# ee453_pcb_Schulz.net
KiCad netlist of a schematic drawn in Altium Designer
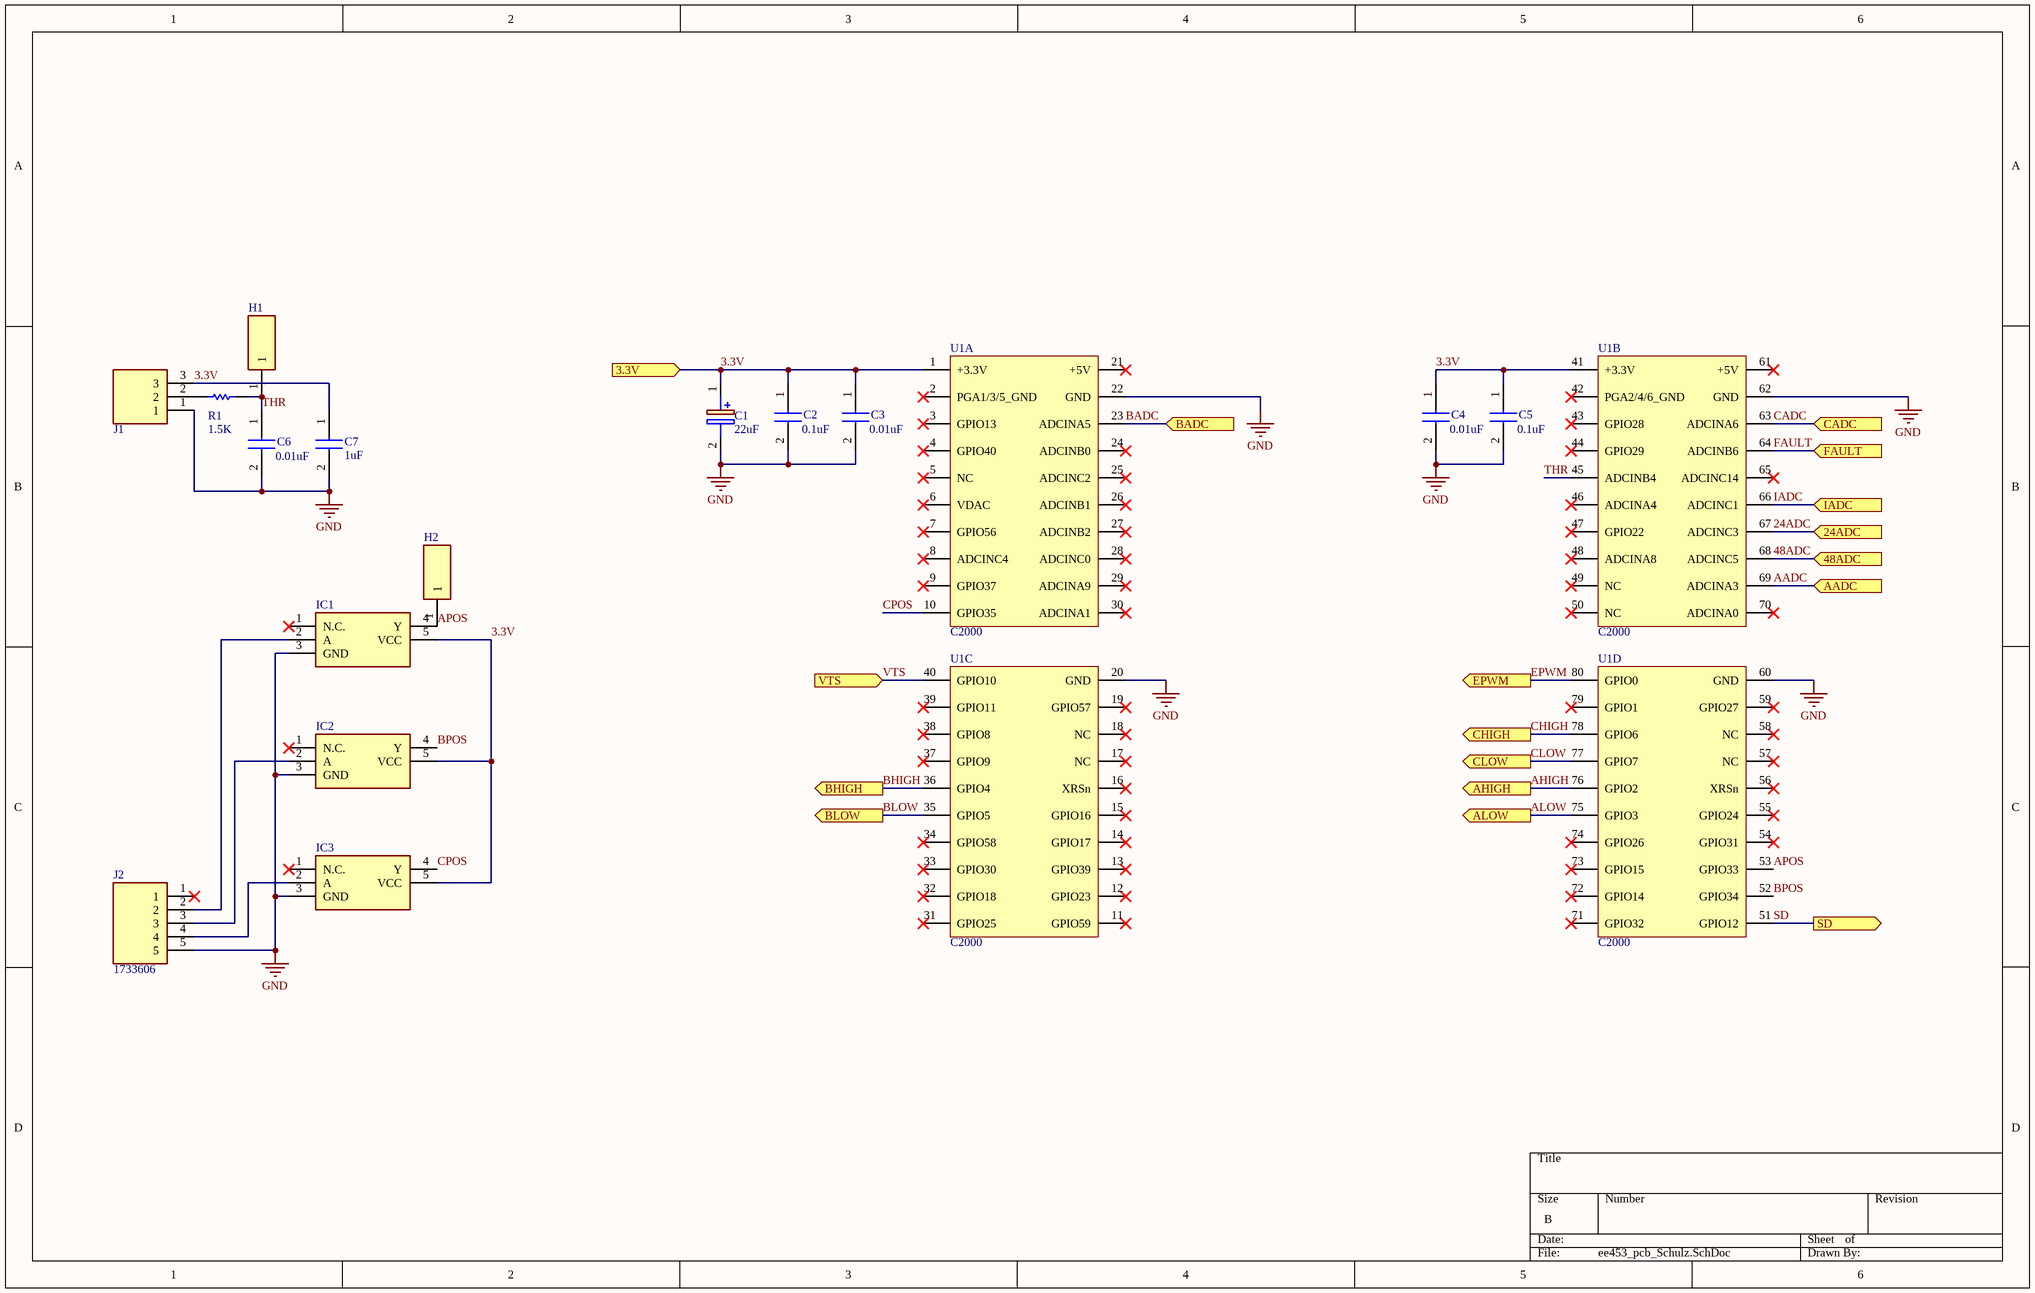
[diagram p0: ee453_pcb_Schulz.SchDoc]

(export (version "E")
  (design (tool "Eeschema 10.0.6"))
  (components
    (comp (ref "C1")
      (value "22uF")
      (footprint "CAPPRD250W50D800H800")
      (description "Capacitor Polarised 10V")
      (fields
        (field (name "MANUFACTURER_PART_NUMBER") "ECE-A1AKA220I")
        (field (name "MOUSER PART NUMBER") "667-ECE-A1AKA220I")
      )
      (libsource (lib "ee_453_Schulz") (part "ECE-A1AKA220I"))
    )
    (comp (ref "C2")
      (value "0.1uF")
      (footprint "CAPC1005X55N")
      (description "Capacitor 10V")
      (fields
        (field (name "MANUFACTURER_PART_NUMBER") "CC0402KRX7R6BB104")
        (field (name "MOUSER PART NUMBER") "603-CC402KRX7R6BB104")
      )
      (libsource (lib "ee_453_Schulz") (part "CC0402KRX7R6BB104"))
    )
    (comp (ref "C3")
      (value "0.01uF")
      (footprint "CAPC0603X33N")
      (description "Capacitor 10V")
      (fields
        (field (name "MANUFACTURER_PART_NUMBER") "GRM033R71A103KA01D")
        (field (name "MOUSER PART NUMBER") "81-GRM033R71A103KA1D")
      )
      (libsource (lib "ee_453_Schulz") (part "GRM033R71A103KA01D"))
    )
    (comp (ref "C4")
      (value "0.01uF")
      (footprint "CAPC0603X33N")
      (description "Capacitor 10V")
      (fields
        (field (name "MANUFACTURER_PART_NUMBER") "GRM033R71A103KA01D")
        (field (name "MOUSER PART NUMBER") "81-GRM033R71A103KA1D")
      )
      (libsource (lib "ee_453_Schulz") (part "GRM033R71A103KA01D"))
    )
    (comp (ref "C5")
      (value "0.1uF")
      (footprint "CAPC1005X55N")
      (description "Capacitor 10V")
      (fields
        (field (name "MANUFACTURER_PART_NUMBER") "CC0402KRX7R6BB104")
        (field (name "MOUSER PART NUMBER") "603-CC402KRX7R6BB104")
      )
      (libsource (lib "ee_453_Schulz") (part "CC0402KRX7R6BB104"))
    )
    (comp (ref "C6")
      (value "0.01uF")
      (footprint "C315C103K5R5TA7990")
      (description "Capacitor 50V")
      (fields (field (name "MANUFACTURER_PART_NUMBER") "C315C103K5R5TA7990"))
      (libsource (lib "ee_453_Schulz") (part "C315C103K5R5TA7990"))
    )
    (comp (ref "C7")
      (value "1uF")
      (footprint "C330C105K5R5TA")
      (description "Capacitor 50V")
      (fields
        (field (name "MANUFACTURER_PART_NUMBER") "C330C105K5R5TA")
        (field (name "MOUSER PART NUMBER") "80-C330C105K5R")
      )
      (libsource (lib "ee_453_Schulz") (part "C330C105K5R5TA"))
    )
    (comp (ref "H1")
      (value "5003")
      (footprint "5003")
      (description "Hardware")
      (fields (field (name "MOUSER PART NUMBER") "534-5003"))
      (libsource (lib "ee_453_Schulz") (part "5003"))
    )
    (comp (ref "H2")
      (value "5003")
      (footprint "5003")
      (description "Hardware")
      (fields (field (name "MOUSER PART NUMBER") "534-5003"))
      (libsource (lib "ee_453_Schulz") (part "5003"))
    )
    (comp (ref "IC1")
      (value "SN74LV1T34DBVRG4")
      (footprint "SOT95P280X145-5N")
      (description "Integrated Circuit")
      (fields (field (name "MOUSER PART NUMBER") "595-SN74LV1T34DBVRG4"))
      (libsource (lib "ee_453_Schulz") (part "SN74LV1T34DBVRG4"))
    )
    (comp (ref "IC2")
      (value "SN74LV1T34DBVRG4")
      (footprint "SOT95P280X145-5N")
      (description "Integrated Circuit")
      (fields (field (name "MOUSER PART NUMBER") "595-SN74LV1T34DBVRG4"))
      (libsource (lib "ee_453_Schulz") (part "SN74LV1T34DBVRG4"))
    )
    (comp (ref "IC3")
      (value "SN74LV1T34DBVRG4")
      (footprint "SOT95P280X145-5N")
      (description "Integrated Circuit")
      (fields (field (name "MOUSER PART NUMBER") "595-SN74LV1T34DBVRG4"))
      (libsource (lib "ee_453_Schulz") (part "SN74LV1T34DBVRG4"))
    )
    (comp (ref "J1")
      (value "1985917")
      (footprint "1985917")
      (description "Connector")
      (fields (field (name "MOUSER PART NUMBER") "651-1985917") (field (name "RS PART NUMBER") "8552938"))
      (libsource (lib "ee_453_Schulz") (part "1985917"))
    )
    (comp (ref "J2")
      (value "1733606")
      (footprint "SHDR5W110P0X500_1X5_2532X7360X1530P")
      (description "Connector")
      (fields (field (name "MOUSER PART NUMBER") "651-1733606") (field (name "RS PART NUMBER") "8818799"))
      (libsource (lib "ee_453_Schulz") (part "1733606"))
    )
    (comp (ref "R1")
      (value "1.5K")
      (footprint "AXIAL-0.3")
      (description "Resistor")
      (fields (field (name "Comment") "Res1") (field (name "PUBLISHER") "Altium Limited"))
      (libsource (lib "Miscellaneous Devices") (part "Res1"))
    )
    (comp (ref "U1")
      (value "C2000")
      (footprint "C2000")
      (description "F280049C")
      (libsource (lib "ee_453_Schulz") (part "C2000"))
    )
  )
  (nets
    (net (code "1") (name "/3.3V") (class "Default")
      (node (ref "C1") (pin "1") (pinfunction "+_1") (pintype "passive"))
      (node (ref "C2") (pin "1") (pinfunction "1_1") (pintype "passive"))
      (node (ref "C3") (pin "1") (pinfunction "1_1") (pintype "passive"))
      (node (ref "C4") (pin "1") (pinfunction "1_1") (pintype "passive"))
      (node (ref "C5") (pin "1") (pinfunction "1_1") (pintype "passive"))
      (node (ref "C7") (pin "1") (pinfunction "1_1") (pintype "passive"))
      (node (ref "IC1") (pin "5") (pinfunction "VCC_5") (pintype "passive"))
      (node (ref "IC2") (pin "5") (pinfunction "VCC_5") (pintype "passive"))
      (node (ref "IC3") (pin "5") (pinfunction "VCC_5") (pintype "passive"))
      (node (ref "J1") (pin "3") (pinfunction "3_3") (pintype "passive"))
      (node (ref "U1") (pin "1") (pinfunction "+3.3V_1") (pintype "passive"))
      (node (ref "U1") (pin "41") (pinfunction "+3.3V_41") (pintype "passive"))
    )
    (net (code "2") (name "/24ADC") (class "Default")
      (node (ref "U1") (pin "67") (pinfunction "ADCINC3_67") (pintype "passive"))
    )
    (net (code "3") (name "/48ADC") (class "Default")
      (node (ref "U1") (pin "68") (pinfunction "ADCINC5_68") (pintype "passive"))
    )
    (net (code "4") (name "/AADC") (class "Default")
      (node (ref "U1") (pin "69") (pinfunction "ADCINA3_69") (pintype "passive"))
    )
    (net (code "5") (name "/AHIGH") (class "Default")
      (node (ref "U1") (pin "76") (pinfunction "GPIO2_76") (pintype "passive"))
    )
    (net (code "6") (name "/ALOW") (class "Default")
      (node (ref "U1") (pin "75") (pinfunction "GPIO3_75") (pintype "passive"))
    )
    (net (code "7") (name "/APOS") (class "Default")
      (node (ref "H2") (pin "1") (pinfunction "1_1") (pintype "passive"))
      (node (ref "IC1") (pin "4") (pinfunction "Y_4") (pintype "passive"))
      (node (ref "U1") (pin "53") (pinfunction "GPIO33_53") (pintype "passive"))
    )
    (net (code "8") (name "/BADC") (class "Default")
      (node (ref "U1") (pin "23") (pinfunction "ADCINA5_23") (pintype "passive"))
    )
    (net (code "9") (name "/BHIGH") (class "Default")
      (node (ref "U1") (pin "36") (pinfunction "GPIO4_36") (pintype "passive"))
    )
    (net (code "10") (name "/BLOW") (class "Default")
      (node (ref "U1") (pin "35") (pinfunction "GPIO5_35") (pintype "passive"))
    )
    (net (code "11") (name "/BPOS") (class "Default")
      (node (ref "IC2") (pin "4") (pinfunction "Y_4") (pintype "passive"))
      (node (ref "U1") (pin "52") (pinfunction "GPIO34_52") (pintype "passive"))
    )
    (net (code "12") (name "/CADC") (class "Default")
      (node (ref "U1") (pin "63") (pinfunction "ADCINA6_63") (pintype "passive"))
    )
    (net (code "13") (name "/CHIGH") (class "Default")
      (node (ref "U1") (pin "78") (pinfunction "GPIO6_78") (pintype "passive"))
    )
    (net (code "14") (name "/CLOW") (class "Default")
      (node (ref "U1") (pin "77") (pinfunction "GPIO7_77") (pintype "passive"))
    )
    (net (code "15") (name "/CPOS") (class "Default")
      (node (ref "IC3") (pin "4") (pinfunction "Y_4") (pintype "passive"))
      (node (ref "U1") (pin "10") (pinfunction "GPIO35_10") (pintype "passive"))
    )
    (net (code "16") (name "/EPWM") (class "Default")
      (node (ref "U1") (pin "80") (pinfunction "GPIO0_80") (pintype "passive"))
    )
    (net (code "17") (name "/FAULT") (class "Default")
      (node (ref "U1") (pin "64") (pinfunction "ADCINB6_64") (pintype "passive"))
    )
    (net (code "18") (name "/IADC") (class "Default")
      (node (ref "U1") (pin "66") (pinfunction "ADCINC1_66") (pintype "passive"))
    )
    (net (code "19") (name "/SD") (class "Default")
      (node (ref "U1") (pin "51") (pinfunction "GPIO12_51") (pintype "passive"))
    )
    (net (code "20") (name "/THR") (class "Default")
      (node (ref "C6") (pin "1") (pinfunction "1_1") (pintype "passive"))
      (node (ref "H1") (pin "1") (pinfunction "1_1") (pintype "passive"))
      (node (ref "R1") (pin "1") (pinfunction "1_1") (pintype "passive"))
      (node (ref "U1") (pin "45") (pinfunction "ADCINB4_45") (pintype "passive"))
    )
    (net (code "21") (name "/VTS") (class "Default")
      (node (ref "U1") (pin "40") (pinfunction "GPIO10_40") (pintype "passive"))
    )
    (net (code "22") (name "GND") (class "Default")
      (node (ref "C1") (pin "2") (pinfunction "-_2") (pintype "passive"))
      (node (ref "C2") (pin "2") (pinfunction "2_2") (pintype "passive"))
      (node (ref "C3") (pin "2") (pinfunction "2_2") (pintype "passive"))
      (node (ref "C4") (pin "2") (pinfunction "2_2") (pintype "passive"))
      (node (ref "C5") (pin "2") (pinfunction "2_2") (pintype "passive"))
      (node (ref "C6") (pin "2") (pinfunction "2_2") (pintype "passive"))
      (node (ref "C7") (pin "2") (pinfunction "2_2") (pintype "passive"))
      (node (ref "IC1") (pin "3") (pinfunction "GND_3") (pintype "passive"))
      (node (ref "IC2") (pin "3") (pinfunction "GND_3") (pintype "passive"))
      (node (ref "IC3") (pin "3") (pinfunction "GND_3") (pintype "passive"))
      (node (ref "J1") (pin "1") (pinfunction "1_1") (pintype "passive"))
      (node (ref "J2") (pin "5") (pinfunction "5_5") (pintype "passive"))
      (node (ref "U1") (pin "20") (pinfunction "GND_20") (pintype "passive"))
      (node (ref "U1") (pin "22") (pinfunction "GND_22") (pintype "passive"))
      (node (ref "U1") (pin "60") (pinfunction "GND_60") (pintype "passive"))
      (node (ref "U1") (pin "62") (pinfunction "GND_62") (pintype "passive"))
    )
    (net (code "23") (name "Net-(IC1-A)") (class "Default")
      (node (ref "IC1") (pin "2") (pinfunction "A_2") (pintype "passive"))
      (node (ref "J2") (pin "2") (pinfunction "2_2") (pintype "passive"))
    )
    (net (code "24") (name "Net-(IC2-A)") (class "Default")
      (node (ref "IC2") (pin "2") (pinfunction "A_2") (pintype "passive"))
      (node (ref "J2") (pin "3") (pinfunction "3_3") (pintype "passive"))
    )
    (net (code "25") (name "Net-(IC3-A)") (class "Default")
      (node (ref "IC3") (pin "2") (pinfunction "A_2") (pintype "passive"))
      (node (ref "J2") (pin "4") (pinfunction "4_4") (pintype "passive"))
    )
    (net (code "26") (name "Net-(J1-Pad2)") (class "Default")
      (node (ref "J1") (pin "2") (pinfunction "2_2") (pintype "passive"))
      (node (ref "R1") (pin "2") (pinfunction "2_2") (pintype "passive"))
    )
    (net (code "27") (name "unconnected-(IC1-N.C.-Pad1)") (class "Default")
      (node (ref "IC1") (pin "1") (pinfunction "N.C._1") (pintype "passive+no_connect"))
    )
    (net (code "28") (name "unconnected-(IC2-N.C.-Pad1)") (class "Default")
      (node (ref "IC2") (pin "1") (pinfunction "N.C._1") (pintype "passive+no_connect"))
    )
    (net (code "29") (name "unconnected-(IC3-N.C.-Pad1)") (class "Default")
      (node (ref "IC3") (pin "1") (pinfunction "N.C._1") (pintype "passive+no_connect"))
    )
    (net (code "30") (name "unconnected-(J2-Pad1)") (class "Default")
      (node (ref "J2") (pin "1") (pinfunction "1_1") (pintype "passive+no_connect"))
    )
    (net (code "31") (name "unconnected-(U1A-+5V-Pad21)") (class "Default")
      (node (ref "U1") (pin "21") (pinfunction "+5V_21") (pintype "passive+no_connect"))
    )
    (net (code "32") (name "unconnected-(U1A-ADCINA1-Pad30)") (class "Default")
      (node (ref "U1") (pin "30") (pinfunction "ADCINA1_30") (pintype "passive+no_connect"))
    )
    (net (code "33") (name "unconnected-(U1A-ADCINA9-Pad29)") (class "Default")
      (node (ref "U1") (pin "29") (pinfunction "ADCINA9_29") (pintype "passive+no_connect"))
    )
    (net (code "34") (name "unconnected-(U1A-ADCINB0-Pad24)") (class "Default")
      (node (ref "U1") (pin "24") (pinfunction "ADCINB0_24") (pintype "passive+no_connect"))
    )
    (net (code "35") (name "unconnected-(U1A-ADCINB1-Pad26)") (class "Default")
      (node (ref "U1") (pin "26") (pinfunction "ADCINB1_26") (pintype "passive+no_connect"))
    )
    (net (code "36") (name "unconnected-(U1A-ADCINB2-Pad27)") (class "Default")
      (node (ref "U1") (pin "27") (pinfunction "ADCINB2_27") (pintype "passive+no_connect"))
    )
    (net (code "37") (name "unconnected-(U1A-ADCINC0-Pad28)") (class "Default")
      (node (ref "U1") (pin "28") (pinfunction "ADCINC0_28") (pintype "passive+no_connect"))
    )
    (net (code "38") (name "unconnected-(U1A-ADCINC2-Pad25)") (class "Default")
      (node (ref "U1") (pin "25") (pinfunction "ADCINC2_25") (pintype "passive+no_connect"))
    )
    (net (code "39") (name "unconnected-(U1A-ADCINC4-Pad8)") (class "Default")
      (node (ref "U1") (pin "8") (pinfunction "ADCINC4_8") (pintype "passive+no_connect"))
    )
    (net (code "40") (name "unconnected-(U1A-GPIO13-Pad3)") (class "Default")
      (node (ref "U1") (pin "3") (pinfunction "GPIO13_3") (pintype "passive+no_connect"))
    )
    (net (code "41") (name "unconnected-(U1A-GPIO37-Pad9)") (class "Default")
      (node (ref "U1") (pin "9") (pinfunction "GPIO37_9") (pintype "passive+no_connect"))
    )
    (net (code "42") (name "unconnected-(U1A-GPIO40-Pad4)") (class "Default")
      (node (ref "U1") (pin "4") (pinfunction "GPIO40_4") (pintype "passive+no_connect"))
    )
    (net (code "43") (name "unconnected-(U1A-GPIO56-Pad7)") (class "Default")
      (node (ref "U1") (pin "7") (pinfunction "GPIO56_7") (pintype "passive+no_connect"))
    )
    (net (code "44") (name "unconnected-(U1A-NC-Pad5)") (class "Default")
      (node (ref "U1") (pin "5") (pinfunction "NC_5") (pintype "passive+no_connect"))
    )
    (net (code "45") (name "unconnected-(U1A-PGA1{slash}3{slash}5_GND-Pad2)") (class "Default")
      (node (ref "U1") (pin "2") (pinfunction "PGA1/3/5_GND_2") (pintype "passive+no_connect"))
    )
    (net (code "46") (name "unconnected-(U1A-VDAC-Pad6)") (class "Default")
      (node (ref "U1") (pin "6") (pinfunction "VDAC_6") (pintype "passive+no_connect"))
    )
    (net (code "47") (name "unconnected-(U1B-+5V-Pad61)") (class "Default")
      (node (ref "U1") (pin "61") (pinfunction "+5V_61") (pintype "passive+no_connect"))
    )
    (net (code "48") (name "unconnected-(U1B-ADCINA0-Pad70)") (class "Default")
      (node (ref "U1") (pin "70") (pinfunction "ADCINA0_70") (pintype "passive+no_connect"))
    )
    (net (code "49") (name "unconnected-(U1B-ADCINA4-Pad46)") (class "Default")
      (node (ref "U1") (pin "46") (pinfunction "ADCINA4_46") (pintype "passive+no_connect"))
    )
    (net (code "50") (name "unconnected-(U1B-ADCINA8-Pad48)") (class "Default")
      (node (ref "U1") (pin "48") (pinfunction "ADCINA8_48") (pintype "passive+no_connect"))
    )
    (net (code "51") (name "unconnected-(U1B-ADCINC14-Pad65)") (class "Default")
      (node (ref "U1") (pin "65") (pinfunction "ADCINC14_65") (pintype "passive+no_connect"))
    )
    (net (code "52") (name "unconnected-(U1B-GPIO22-Pad47)") (class "Default")
      (node (ref "U1") (pin "47") (pinfunction "GPIO22_47") (pintype "passive+no_connect"))
    )
    (net (code "53") (name "unconnected-(U1B-GPIO28-Pad43)") (class "Default")
      (node (ref "U1") (pin "43") (pinfunction "GPIO28_43") (pintype "passive+no_connect"))
    )
    (net (code "54") (name "unconnected-(U1B-GPIO29-Pad44)") (class "Default")
      (node (ref "U1") (pin "44") (pinfunction "GPIO29_44") (pintype "passive+no_connect"))
    )
    (net (code "55") (name "unconnected-(U1B-NC-Pad49)") (class "Default")
      (node (ref "U1") (pin "49") (pinfunction "NC_49") (pintype "passive+no_connect"))
    )
    (net (code "56") (name "unconnected-(U1B-NC-Pad50)") (class "Default")
      (node (ref "U1") (pin "50") (pinfunction "NC_50") (pintype "passive+no_connect"))
    )
    (net (code "57") (name "unconnected-(U1B-PGA2{slash}4{slash}6_GND-Pad42)") (class "Default")
      (node (ref "U1") (pin "42") (pinfunction "PGA2/4/6_GND_42") (pintype "passive+no_connect"))
    )
    (net (code "58") (name "unconnected-(U1C-GPIO8-Pad38)") (class "Default")
      (node (ref "U1") (pin "38") (pinfunction "GPIO8_38") (pintype "passive+no_connect"))
    )
    (net (code "59") (name "unconnected-(U1C-GPIO9-Pad37)") (class "Default")
      (node (ref "U1") (pin "37") (pinfunction "GPIO9_37") (pintype "passive+no_connect"))
    )
    (net (code "60") (name "unconnected-(U1C-GPIO11-Pad39)") (class "Default")
      (node (ref "U1") (pin "39") (pinfunction "GPIO11_39") (pintype "passive+no_connect"))
    )
    (net (code "61") (name "unconnected-(U1C-GPIO16-Pad15)") (class "Default")
      (node (ref "U1") (pin "15") (pinfunction "GPIO16_15") (pintype "passive+no_connect"))
    )
    (net (code "62") (name "unconnected-(U1C-GPIO17-Pad14)") (class "Default")
      (node (ref "U1") (pin "14") (pinfunction "GPIO17_14") (pintype "passive+no_connect"))
    )
    (net (code "63") (name "unconnected-(U1C-GPIO18-Pad32)") (class "Default")
      (node (ref "U1") (pin "32") (pinfunction "GPIO18_32") (pintype "passive+no_connect"))
    )
    (net (code "64") (name "unconnected-(U1C-GPIO23-Pad12)") (class "Default")
      (node (ref "U1") (pin "12") (pinfunction "GPIO23_12") (pintype "passive+no_connect"))
    )
    (net (code "65") (name "unconnected-(U1C-GPIO25-Pad31)") (class "Default")
      (node (ref "U1") (pin "31") (pinfunction "GPIO25_31") (pintype "passive+no_connect"))
    )
    (net (code "66") (name "unconnected-(U1C-GPIO30-Pad33)") (class "Default")
      (node (ref "U1") (pin "33") (pinfunction "GPIO30_33") (pintype "passive+no_connect"))
    )
    (net (code "67") (name "unconnected-(U1C-GPIO39-Pad13)") (class "Default")
      (node (ref "U1") (pin "13") (pinfunction "GPIO39_13") (pintype "passive+no_connect"))
    )
    (net (code "68") (name "unconnected-(U1C-GPIO57-Pad19)") (class "Default")
      (node (ref "U1") (pin "19") (pinfunction "GPIO57_19") (pintype "passive+no_connect"))
    )
    (net (code "69") (name "unconnected-(U1C-GPIO58-Pad34)") (class "Default")
      (node (ref "U1") (pin "34") (pinfunction "GPIO58_34") (pintype "passive+no_connect"))
    )
    (net (code "70") (name "unconnected-(U1C-GPIO59-Pad11)") (class "Default")
      (node (ref "U1") (pin "11") (pinfunction "GPIO59_11") (pintype "passive+no_connect"))
    )
    (net (code "71") (name "unconnected-(U1C-NC-Pad17)") (class "Default")
      (node (ref "U1") (pin "17") (pinfunction "NC_17") (pintype "passive+no_connect"))
    )
    (net (code "72") (name "unconnected-(U1C-NC-Pad18)") (class "Default")
      (node (ref "U1") (pin "18") (pinfunction "NC_18") (pintype "passive+no_connect"))
    )
    (net (code "73") (name "unconnected-(U1C-XRSn-Pad16)") (class "Default")
      (node (ref "U1") (pin "16") (pinfunction "XRSn_16") (pintype "passive+no_connect"))
    )
    (net (code "74") (name "unconnected-(U1D-GPIO1-Pad79)") (class "Default")
      (node (ref "U1") (pin "79") (pinfunction "GPIO1_79") (pintype "passive+no_connect"))
    )
    (net (code "75") (name "unconnected-(U1D-GPIO14-Pad72)") (class "Default")
      (node (ref "U1") (pin "72") (pinfunction "GPIO14_72") (pintype "passive+no_connect"))
    )
    (net (code "76") (name "unconnected-(U1D-GPIO15-Pad73)") (class "Default")
      (node (ref "U1") (pin "73") (pinfunction "GPIO15_73") (pintype "passive+no_connect"))
    )
    (net (code "77") (name "unconnected-(U1D-GPIO24-Pad55)") (class "Default")
      (node (ref "U1") (pin "55") (pinfunction "GPIO24_55") (pintype "passive+no_connect"))
    )
    (net (code "78") (name "unconnected-(U1D-GPIO26-Pad74)") (class "Default")
      (node (ref "U1") (pin "74") (pinfunction "GPIO26_74") (pintype "passive+no_connect"))
    )
    (net (code "79") (name "unconnected-(U1D-GPIO27-Pad59)") (class "Default")
      (node (ref "U1") (pin "59") (pinfunction "GPIO27_59") (pintype "passive+no_connect"))
    )
    (net (code "80") (name "unconnected-(U1D-GPIO31-Pad54)") (class "Default")
      (node (ref "U1") (pin "54") (pinfunction "GPIO31_54") (pintype "passive+no_connect"))
    )
    (net (code "81") (name "unconnected-(U1D-GPIO32-Pad71)") (class "Default")
      (node (ref "U1") (pin "71") (pinfunction "GPIO32_71") (pintype "passive+no_connect"))
    )
    (net (code "82") (name "unconnected-(U1D-NC-Pad57)") (class "Default")
      (node (ref "U1") (pin "57") (pinfunction "NC_57") (pintype "passive+no_connect"))
    )
    (net (code "83") (name "unconnected-(U1D-NC-Pad58)") (class "Default")
      (node (ref "U1") (pin "58") (pinfunction "NC_58") (pintype "passive+no_connect"))
    )
    (net (code "84") (name "unconnected-(U1D-XRSn-Pad56)") (class "Default")
      (node (ref "U1") (pin "56") (pinfunction "XRSn_56") (pintype "passive+no_connect"))
    )
  )
)
